# CM4.net
KiCad netlist of a schematic drawn in Altium Designer
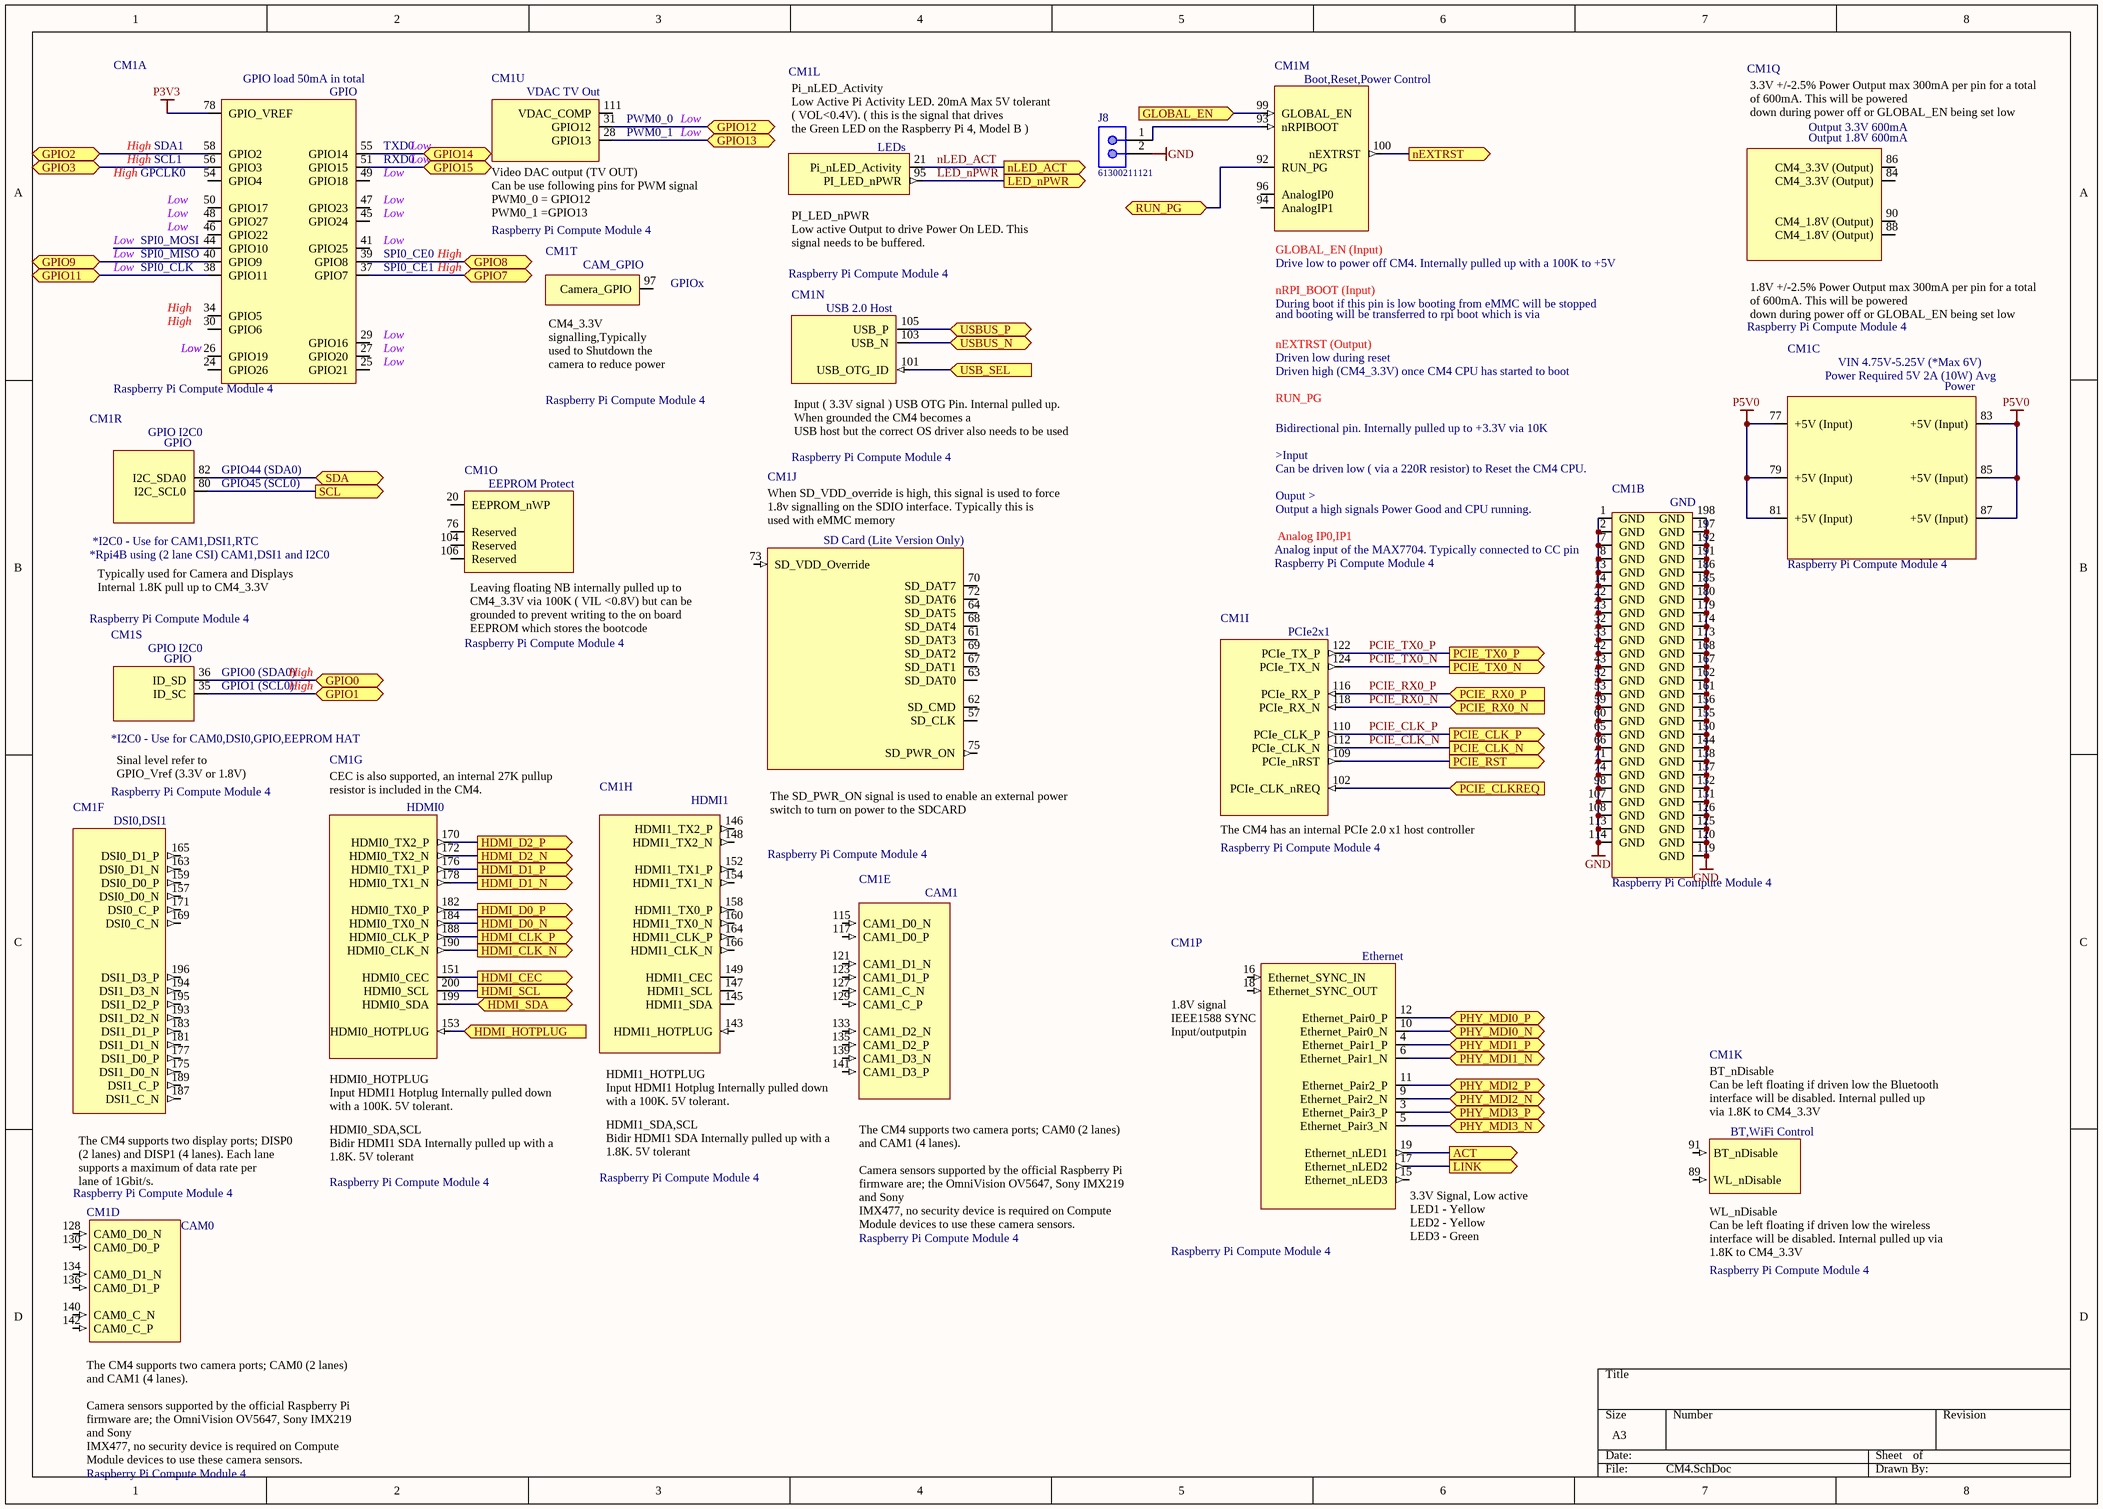
[diagram p0: CM4.SchDoc]

(export (version "E")
  (design (tool "Eeschema 10.0.6"))
  (components
    (comp (ref "CM1")
      (value "Raspberry Pi Compute Module 4")
      (footprint "CM4-DF40HC(3.0)-100DS-0.4v_3mm_1.5mm")
      (description "Raspberry Pi Compute Module 4 by Amornthep Phunsin")
      (libsource (lib "CM4") (part "CM4"))
    )
    (comp (ref "J8")
      (value "61300211121")
      (footprint "61300211121")
      (description "WR-PHD Pin Header, THT, pitch 2.54mm, Single Row, Vertical, 2pin")
      (fields (field (name "PUBLISHER") "Wurth Elektronik"))
      (libsource (lib "ALTIUM-WR-PHD_PIN_HEADER_SOCKET_HEADER-rev19a") (part "61300211121"))
    )
  )
  (nets
    (net (code "1") (name "/ACT") (class "Default")
      (node (ref "CM1") (pin "19") (pinfunction "Ethernet_nLED1_19") (pintype "output"))
    )
    (net (code "2") (name "/GLOBAL_EN") (class "Default")
      (node (ref "CM1") (pin "99") (pinfunction "GLOBAL_EN_99") (pintype "input"))
    )
    (net (code "3") (name "/GPIO0") (class "Default")
      (node (ref "CM1") (pin "36") (pinfunction "ID_SD_36") (pintype "passive"))
    )
    (net (code "4") (name "/GPIO1") (class "Default")
      (node (ref "CM1") (pin "35") (pinfunction "ID_SC_35") (pintype "passive"))
    )
    (net (code "5") (name "/GPIO2") (class "Default")
      (node (ref "CM1") (pin "58") (pinfunction "GPIO2_58") (pintype "passive"))
    )
    (net (code "6") (name "/GPIO3") (class "Default")
      (node (ref "CM1") (pin "56") (pinfunction "GPIO3_56") (pintype "passive"))
    )
    (net (code "7") (name "/GPIO7") (class "Default")
      (node (ref "CM1") (pin "37") (pinfunction "GPIO7_37") (pintype "passive"))
    )
    (net (code "8") (name "/GPIO8") (class "Default")
      (node (ref "CM1") (pin "39") (pinfunction "GPIO8_39") (pintype "passive"))
    )
    (net (code "9") (name "/GPIO9") (class "Default")
      (node (ref "CM1") (pin "40") (pinfunction "GPIO9_40") (pintype "passive"))
    )
    (net (code "10") (name "/GPIO11") (class "Default")
      (node (ref "CM1") (pin "38") (pinfunction "GPIO11_38") (pintype "passive"))
    )
    (net (code "11") (name "/GPIO12") (class "Default")
      (node (ref "CM1") (pin "31") (pinfunction "GPIO12_31") (pintype "passive"))
    )
    (net (code "12") (name "/GPIO13") (class "Default")
      (node (ref "CM1") (pin "28") (pinfunction "GPIO13_28") (pintype "passive"))
    )
    (net (code "13") (name "/GPIO14") (class "Default")
      (node (ref "CM1") (pin "55") (pinfunction "GPIO14_55") (pintype "passive"))
    )
    (net (code "14") (name "/GPIO15") (class "Default")
      (node (ref "CM1") (pin "51") (pinfunction "GPIO15_51") (pintype "passive"))
    )
    (net (code "15") (name "/HDMI_CEC") (class "Default")
      (node (ref "CM1") (pin "151") (pinfunction "HDMI0_CEC_151") (pintype "open_collector"))
    )
    (net (code "16") (name "/HDMI_CLK_N") (class "Default")
      (node (ref "CM1") (pin "190") (pinfunction "HDMI0_CLK_N_190") (pintype "output"))
    )
    (net (code "17") (name "/HDMI_CLK_P") (class "Default")
      (node (ref "CM1") (pin "188") (pinfunction "HDMI0_CLK_P_188") (pintype "output"))
    )
    (net (code "18") (name "/HDMI_D0_N") (class "Default")
      (node (ref "CM1") (pin "184") (pinfunction "HDMI0_TX0_N_184") (pintype "output"))
    )
    (net (code "19") (name "/HDMI_D0_P") (class "Default")
      (node (ref "CM1") (pin "182") (pinfunction "HDMI0_TX0_P_182") (pintype "output"))
    )
    (net (code "20") (name "/HDMI_D1_N") (class "Default")
      (node (ref "CM1") (pin "178") (pinfunction "HDMI0_TX1_N_178") (pintype "output"))
    )
    (net (code "21") (name "/HDMI_D1_P") (class "Default")
      (node (ref "CM1") (pin "176") (pinfunction "HDMI0_TX1_P_176") (pintype "output"))
    )
    (net (code "22") (name "/HDMI_D2_N") (class "Default")
      (node (ref "CM1") (pin "172") (pinfunction "HDMI0_TX2_N_172") (pintype "output"))
    )
    (net (code "23") (name "/HDMI_D2_P") (class "Default")
      (node (ref "CM1") (pin "170") (pinfunction "HDMI0_TX2_P_170") (pintype "output"))
    )
    (net (code "24") (name "/HDMI_HOTPLUG") (class "Default")
      (node (ref "CM1") (pin "153") (pinfunction "HDMI0_HOTPLUG_153") (pintype "input"))
    )
    (net (code "25") (name "/HDMI_SCL") (class "Default")
      (node (ref "CM1") (pin "200") (pinfunction "HDMI0_SCL_200") (pintype "open_collector"))
    )
    (net (code "26") (name "/HDMI_SDA") (class "Default")
      (node (ref "CM1") (pin "199") (pinfunction "HDMI0_SDA_199") (pintype "bidirectional"))
    )
    (net (code "27") (name "/LED_nPWR") (class "Default")
      (node (ref "CM1") (pin "95") (pinfunction "PI_LED_nPWR_95") (pintype "output"))
    )
    (net (code "28") (name "/LINK") (class "Default")
      (node (ref "CM1") (pin "17") (pinfunction "Ethernet_nLED2_17") (pintype "output"))
    )
    (net (code "29") (name "/PCIE_CLKREQ") (class "Default")
      (node (ref "CM1") (pin "102") (pinfunction "PCIe_CLK_nREQ_102") (pintype "input"))
    )
    (net (code "30") (name "/PCIE_CLK_N") (class "Default")
      (node (ref "CM1") (pin "112") (pinfunction "PCIe_CLK_N_112") (pintype "output"))
    )
    (net (code "31") (name "/PCIE_CLK_P") (class "Default")
      (node (ref "CM1") (pin "110") (pinfunction "PCIe_CLK_P_110") (pintype "output"))
    )
    (net (code "32") (name "/PCIE_RST") (class "Default")
      (node (ref "CM1") (pin "109") (pinfunction "PCIe_nRST_109") (pintype "output"))
    )
    (net (code "33") (name "/PCIE_RX0_N") (class "Default")
      (node (ref "CM1") (pin "118") (pinfunction "PCIe_RX_N_118") (pintype "input"))
    )
    (net (code "34") (name "/PCIE_RX0_P") (class "Default")
      (node (ref "CM1") (pin "116") (pinfunction "PCIe_RX_P_116") (pintype "input"))
    )
    (net (code "35") (name "/PCIE_TX0_N") (class "Default")
      (node (ref "CM1") (pin "124") (pinfunction "PCIe_TX_N_124") (pintype "output"))
    )
    (net (code "36") (name "/PCIE_TX0_P") (class "Default")
      (node (ref "CM1") (pin "122") (pinfunction "PCIe_TX_P_122") (pintype "output"))
    )
    (net (code "37") (name "/PHY_MDI0_N") (class "Default")
      (node (ref "CM1") (pin "10") (pinfunction "Ethernet_Pair0_N_10") (pintype "passive"))
    )
    (net (code "38") (name "/PHY_MDI0_P") (class "Default")
      (node (ref "CM1") (pin "12") (pinfunction "Ethernet_Pair0_P_12") (pintype "passive"))
    )
    (net (code "39") (name "/PHY_MDI1_N") (class "Default")
      (node (ref "CM1") (pin "6") (pinfunction "Ethernet_Pair1_N_6") (pintype "passive"))
    )
    (net (code "40") (name "/PHY_MDI1_P") (class "Default")
      (node (ref "CM1") (pin "4") (pinfunction "Ethernet_Pair1_P_4") (pintype "passive"))
    )
    (net (code "41") (name "/PHY_MDI2_N") (class "Default")
      (node (ref "CM1") (pin "9") (pinfunction "Ethernet_Pair2_N_9") (pintype "passive"))
    )
    (net (code "42") (name "/PHY_MDI2_P") (class "Default")
      (node (ref "CM1") (pin "11") (pinfunction "Ethernet_Pair2_P_11") (pintype "passive"))
    )
    (net (code "43") (name "/PHY_MDI3_N") (class "Default")
      (node (ref "CM1") (pin "5") (pinfunction "Ethernet_Pair3_N_5") (pintype "passive"))
    )
    (net (code "44") (name "/PHY_MDI3_P") (class "Default")
      (node (ref "CM1") (pin "3") (pinfunction "Ethernet_Pair3_P_3") (pintype "passive"))
    )
    (net (code "45") (name "/RUN_PG") (class "Default")
      (node (ref "CM1") (pin "92") (pinfunction "RUN_PG_92") (pintype "passive"))
    )
    (net (code "46") (name "/SCL") (class "Default")
      (node (ref "CM1") (pin "80") (pinfunction "I2C_SCL0_80") (pintype "passive"))
    )
    (net (code "47") (name "/SDA") (class "Default")
      (node (ref "CM1") (pin "82") (pinfunction "I2C_SDA0_82") (pintype "passive"))
    )
    (net (code "48") (name "/USBUS_N") (class "Default")
      (node (ref "CM1") (pin "103") (pinfunction "USB_N_103") (pintype "passive"))
    )
    (net (code "49") (name "/USBUS_P") (class "Default")
      (node (ref "CM1") (pin "105") (pinfunction "USB_P_105") (pintype "passive"))
    )
    (net (code "50") (name "/USB_SEL") (class "Default")
      (node (ref "CM1") (pin "101") (pinfunction "USB_OTG_ID_101") (pintype "input"))
    )
    (net (code "51") (name "/nEXTRST") (class "Default")
      (node (ref "CM1") (pin "100") (pinfunction "nEXTRST_100") (pintype "output"))
    )
    (net (code "52") (name "/nLED_ACT") (class "Default")
      (node (ref "CM1") (pin "21") (pinfunction "Pi_nLED_Activity_21") (pintype "open_collector"))
    )
    (net (code "53") (name "GND") (class "Default")
      (node (ref "CM1") (pin "1") (pinfunction "GND_1") (pintype "power_in"))
      (node (ref "CM1") (pin "107") (pinfunction "GND_107") (pintype "power_in"))
      (node (ref "CM1") (pin "108") (pinfunction "GND_108") (pintype "power_in"))
      (node (ref "CM1") (pin "113") (pinfunction "GND_113") (pintype "power_in"))
      (node (ref "CM1") (pin "114") (pinfunction "GND_114") (pintype "power_in"))
      (node (ref "CM1") (pin "119") (pinfunction "GND_119") (pintype "power_in"))
      (node (ref "CM1") (pin "120") (pinfunction "GND_120") (pintype "power_in"))
      (node (ref "CM1") (pin "125") (pinfunction "GND_125") (pintype "power_in"))
      (node (ref "CM1") (pin "126") (pinfunction "GND_126") (pintype "power_in"))
      (node (ref "CM1") (pin "13") (pinfunction "GND_13") (pintype "power_in"))
      (node (ref "CM1") (pin "131") (pinfunction "GND_131") (pintype "power_in"))
      (node (ref "CM1") (pin "132") (pinfunction "GND_132") (pintype "power_in"))
      (node (ref "CM1") (pin "137") (pinfunction "GND_137") (pintype "power_in"))
      (node (ref "CM1") (pin "138") (pinfunction "GND_138") (pintype "power_in"))
      (node (ref "CM1") (pin "14") (pinfunction "GND_14") (pintype "power_in"))
      (node (ref "CM1") (pin "144") (pinfunction "GND_144") (pintype "power_in"))
      (node (ref "CM1") (pin "150") (pinfunction "GND_150") (pintype "power_in"))
      (node (ref "CM1") (pin "155") (pinfunction "GND_155") (pintype "power_in"))
      (node (ref "CM1") (pin "156") (pinfunction "GND_156") (pintype "power_in"))
      (node (ref "CM1") (pin "161") (pinfunction "GND_161") (pintype "power_in"))
      (node (ref "CM1") (pin "162") (pinfunction "GND_162") (pintype "power_in"))
      (node (ref "CM1") (pin "167") (pinfunction "GND_167") (pintype "power_in"))
      (node (ref "CM1") (pin "168") (pinfunction "GND_168") (pintype "power_in"))
      (node (ref "CM1") (pin "173") (pinfunction "GND_173") (pintype "power_in"))
      (node (ref "CM1") (pin "174") (pinfunction "GND_174") (pintype "power_in"))
      (node (ref "CM1") (pin "179") (pinfunction "GND_179") (pintype "power_in"))
      (node (ref "CM1") (pin "180") (pinfunction "GND_180") (pintype "power_in"))
      (node (ref "CM1") (pin "185") (pinfunction "GND_185") (pintype "power_in"))
      (node (ref "CM1") (pin "186") (pinfunction "GND_186") (pintype "power_in"))
      (node (ref "CM1") (pin "191") (pinfunction "GND_191") (pintype "power_in"))
      (node (ref "CM1") (pin "192") (pinfunction "GND_192") (pintype "power_in"))
      (node (ref "CM1") (pin "197") (pinfunction "GND_197") (pintype "power_in"))
      (node (ref "CM1") (pin "198") (pinfunction "GND_198") (pintype "power_in"))
      (node (ref "CM1") (pin "2") (pinfunction "GND_2") (pintype "power_in"))
      (node (ref "CM1") (pin "22") (pinfunction "GND_22") (pintype "power_in"))
      (node (ref "CM1") (pin "23") (pinfunction "GND_23") (pintype "power_in"))
      (node (ref "CM1") (pin "32") (pinfunction "GND_32") (pintype "power_in"))
      (node (ref "CM1") (pin "33") (pinfunction "GND_33") (pintype "power_in"))
      (node (ref "CM1") (pin "42") (pinfunction "GND_42") (pintype "power_in"))
      (node (ref "CM1") (pin "43") (pinfunction "GND_43") (pintype "power_in"))
      (node (ref "CM1") (pin "52") (pinfunction "GND_52") (pintype "power_in"))
      (node (ref "CM1") (pin "53") (pinfunction "GND_53") (pintype "power_in"))
      (node (ref "CM1") (pin "59") (pinfunction "GND_59") (pintype "power_in"))
      (node (ref "CM1") (pin "60") (pinfunction "GND_60") (pintype "power_in"))
      (node (ref "CM1") (pin "65") (pinfunction "GND_65") (pintype "power_in"))
      (node (ref "CM1") (pin "66") (pinfunction "GND_66") (pintype "power_in"))
      (node (ref "CM1") (pin "7") (pinfunction "GND_7") (pintype "power_in"))
      (node (ref "CM1") (pin "71") (pinfunction "GND_71") (pintype "power_in"))
      (node (ref "CM1") (pin "74") (pinfunction "GND_74") (pintype "power_in"))
      (node (ref "CM1") (pin "8") (pinfunction "GND_8") (pintype "power_in"))
      (node (ref "CM1") (pin "98") (pinfunction "GND_98") (pintype "power_in"))
      (node (ref "J8") (pin "2") (pinfunction "2_2") (pintype "passive"))
    )
    (net (code "54") (name "Net-(CM1M-nRPIBOOT)") (class "Default")
      (node (ref "CM1") (pin "93") (pinfunction "nRPIBOOT_93") (pintype "input"))
      (node (ref "J8") (pin "1") (pinfunction "1_1") (pintype "passive"))
    )
    (net (code "55") (name "P3V3") (class "Default")
      (node (ref "CM1") (pin "78") (pinfunction "GPIO_VREF_78") (pintype "power_in"))
    )
    (net (code "56") (name "P5V0") (class "Default")
      (node (ref "CM1") (pin "77") (pinfunction "+5V_(Input)_77") (pintype "power_in"))
      (node (ref "CM1") (pin "79") (pinfunction "+5V_(Input)_79") (pintype "power_in"))
      (node (ref "CM1") (pin "81") (pinfunction "+5V_(Input)_81") (pintype "power_in"))
      (node (ref "CM1") (pin "83") (pinfunction "+5V_(Input)_83") (pintype "power_in"))
      (node (ref "CM1") (pin "85") (pinfunction "+5V_(Input)_85") (pintype "power_in"))
      (node (ref "CM1") (pin "87") (pinfunction "+5V_(Input)_87") (pintype "power_in"))
    )
    (net (code "57") (name "unconnected-(CM1A-GPIO4-Pad54)") (class "Default")
      (node (ref "CM1") (pin "54") (pinfunction "GPIO4_54") (pintype "passive"))
    )
    (net (code "58") (name "unconnected-(CM1A-GPIO5-Pad34)") (class "Default")
      (node (ref "CM1") (pin "34") (pinfunction "GPIO5_34") (pintype "passive"))
    )
    (net (code "59") (name "unconnected-(CM1A-GPIO6-Pad30)") (class "Default")
      (node (ref "CM1") (pin "30") (pinfunction "GPIO6_30") (pintype "passive"))
    )
    (net (code "60") (name "unconnected-(CM1A-GPIO10-Pad44)") (class "Default")
      (node (ref "CM1") (pin "44") (pinfunction "GPIO10_44") (pintype "passive"))
    )
    (net (code "61") (name "unconnected-(CM1A-GPIO16-Pad29)") (class "Default")
      (node (ref "CM1") (pin "29") (pinfunction "GPIO16_29") (pintype "passive"))
    )
    (net (code "62") (name "unconnected-(CM1A-GPIO17-Pad50)") (class "Default")
      (node (ref "CM1") (pin "50") (pinfunction "GPIO17_50") (pintype "passive"))
    )
    (net (code "63") (name "unconnected-(CM1A-GPIO18-Pad49)") (class "Default")
      (node (ref "CM1") (pin "49") (pinfunction "GPIO18_49") (pintype "passive"))
    )
    (net (code "64") (name "unconnected-(CM1A-GPIO19-Pad26)") (class "Default")
      (node (ref "CM1") (pin "26") (pinfunction "GPIO19_26") (pintype "passive"))
    )
    (net (code "65") (name "unconnected-(CM1A-GPIO20-Pad27)") (class "Default")
      (node (ref "CM1") (pin "27") (pinfunction "GPIO20_27") (pintype "passive"))
    )
    (net (code "66") (name "unconnected-(CM1A-GPIO21-Pad25)") (class "Default")
      (node (ref "CM1") (pin "25") (pinfunction "GPIO21_25") (pintype "passive"))
    )
    (net (code "67") (name "unconnected-(CM1A-GPIO22-Pad46)") (class "Default")
      (node (ref "CM1") (pin "46") (pinfunction "GPIO22_46") (pintype "passive"))
    )
    (net (code "68") (name "unconnected-(CM1A-GPIO23-Pad47)") (class "Default")
      (node (ref "CM1") (pin "47") (pinfunction "GPIO23_47") (pintype "passive"))
    )
    (net (code "69") (name "unconnected-(CM1A-GPIO24-Pad45)") (class "Default")
      (node (ref "CM1") (pin "45") (pinfunction "GPIO24_45") (pintype "passive"))
    )
    (net (code "70") (name "unconnected-(CM1A-GPIO25-Pad41)") (class "Default")
      (node (ref "CM1") (pin "41") (pinfunction "GPIO25_41") (pintype "passive"))
    )
    (net (code "71") (name "unconnected-(CM1A-GPIO26-Pad24)") (class "Default")
      (node (ref "CM1") (pin "24") (pinfunction "GPIO26_24") (pintype "passive"))
    )
    (net (code "72") (name "unconnected-(CM1A-GPIO27-Pad48)") (class "Default")
      (node (ref "CM1") (pin "48") (pinfunction "GPIO27_48") (pintype "passive"))
    )
    (net (code "73") (name "unconnected-(CM1D-CAM0_C_N-Pad140)") (class "Default")
      (node (ref "CM1") (pin "140") (pinfunction "CAM0_C_N_140") (pintype "input"))
    )
    (net (code "74") (name "unconnected-(CM1D-CAM0_C_P-Pad142)") (class "Default")
      (node (ref "CM1") (pin "142") (pinfunction "CAM0_C_P_142") (pintype "input"))
    )
    (net (code "75") (name "unconnected-(CM1D-CAM0_D0_N-Pad128)") (class "Default")
      (node (ref "CM1") (pin "128") (pinfunction "CAM0_D0_N_128") (pintype "input"))
    )
    (net (code "76") (name "unconnected-(CM1D-CAM0_D0_P-Pad130)") (class "Default")
      (node (ref "CM1") (pin "130") (pinfunction "CAM0_D0_P_130") (pintype "input"))
    )
    (net (code "77") (name "unconnected-(CM1D-CAM0_D1_N-Pad134)") (class "Default")
      (node (ref "CM1") (pin "134") (pinfunction "CAM0_D1_N_134") (pintype "input"))
    )
    (net (code "78") (name "unconnected-(CM1D-CAM0_D1_P-Pad136)") (class "Default")
      (node (ref "CM1") (pin "136") (pinfunction "CAM0_D1_P_136") (pintype "input"))
    )
    (net (code "79") (name "unconnected-(CM1E-CAM1_C_N-Pad127)") (class "Default")
      (node (ref "CM1") (pin "127") (pinfunction "CAM1_C_N_127") (pintype "input"))
    )
    (net (code "80") (name "unconnected-(CM1E-CAM1_C_P-Pad129)") (class "Default")
      (node (ref "CM1") (pin "129") (pinfunction "CAM1_C_P_129") (pintype "input"))
    )
    (net (code "81") (name "unconnected-(CM1E-CAM1_D0_N-Pad115)") (class "Default")
      (node (ref "CM1") (pin "115") (pinfunction "CAM1_D0_N_115") (pintype "input"))
    )
    (net (code "82") (name "unconnected-(CM1E-CAM1_D0_P-Pad117)") (class "Default")
      (node (ref "CM1") (pin "117") (pinfunction "CAM1_D0_P_117") (pintype "input"))
    )
    (net (code "83") (name "unconnected-(CM1E-CAM1_D1_N-Pad121)") (class "Default")
      (node (ref "CM1") (pin "121") (pinfunction "CAM1_D1_N_121") (pintype "input"))
    )
    (net (code "84") (name "unconnected-(CM1E-CAM1_D1_P-Pad123)") (class "Default")
      (node (ref "CM1") (pin "123") (pinfunction "CAM1_D1_P_123") (pintype "input"))
    )
    (net (code "85") (name "unconnected-(CM1E-CAM1_D2_N-Pad133)") (class "Default")
      (node (ref "CM1") (pin "133") (pinfunction "CAM1_D2_N_133") (pintype "input"))
    )
    (net (code "86") (name "unconnected-(CM1E-CAM1_D2_P-Pad135)") (class "Default")
      (node (ref "CM1") (pin "135") (pinfunction "CAM1_D2_P_135") (pintype "input"))
    )
    (net (code "87") (name "unconnected-(CM1E-CAM1_D3_N-Pad139)") (class "Default")
      (node (ref "CM1") (pin "139") (pinfunction "CAM1_D3_N_139") (pintype "input"))
    )
    (net (code "88") (name "unconnected-(CM1E-CAM1_D3_P-Pad141)") (class "Default")
      (node (ref "CM1") (pin "141") (pinfunction "CAM1_D3_P_141") (pintype "input"))
    )
    (net (code "89") (name "unconnected-(CM1F-DSI0_C_N-Pad169)") (class "Default")
      (node (ref "CM1") (pin "169") (pinfunction "DSI0_C_N_169") (pintype "output"))
    )
    (net (code "90") (name "unconnected-(CM1F-DSI0_C_P-Pad171)") (class "Default")
      (node (ref "CM1") (pin "171") (pinfunction "DSI0_C_P_171") (pintype "output"))
    )
    (net (code "91") (name "unconnected-(CM1F-DSI0_D0_N-Pad157)") (class "Default")
      (node (ref "CM1") (pin "157") (pinfunction "DSI0_D0_N_157") (pintype "output"))
    )
    (net (code "92") (name "unconnected-(CM1F-DSI0_D0_P-Pad159)") (class "Default")
      (node (ref "CM1") (pin "159") (pinfunction "DSI0_D0_P_159") (pintype "output"))
    )
    (net (code "93") (name "unconnected-(CM1F-DSI0_D1_N-Pad163)") (class "Default")
      (node (ref "CM1") (pin "163") (pinfunction "DSI0_D1_N_163") (pintype "output"))
    )
    (net (code "94") (name "unconnected-(CM1F-DSI0_D1_P-Pad165)") (class "Default")
      (node (ref "CM1") (pin "165") (pinfunction "DSI0_D1_P_165") (pintype "output"))
    )
    (net (code "95") (name "unconnected-(CM1F-DSI1_C_N-Pad187)") (class "Default")
      (node (ref "CM1") (pin "187") (pinfunction "DSI1_C_N_187") (pintype "output"))
    )
    (net (code "96") (name "unconnected-(CM1F-DSI1_C_P-Pad189)") (class "Default")
      (node (ref "CM1") (pin "189") (pinfunction "DSI1_C_P_189") (pintype "output"))
    )
    (net (code "97") (name "unconnected-(CM1F-DSI1_D0_N-Pad175)") (class "Default")
      (node (ref "CM1") (pin "175") (pinfunction "DSI1_D0_N_175") (pintype "output"))
    )
    (net (code "98") (name "unconnected-(CM1F-DSI1_D0_P-Pad177)") (class "Default")
      (node (ref "CM1") (pin "177") (pinfunction "DSI1_D0_P_177") (pintype "output"))
    )
    (net (code "99") (name "unconnected-(CM1F-DSI1_D1_N-Pad181)") (class "Default")
      (node (ref "CM1") (pin "181") (pinfunction "DSI1_D1_N_181") (pintype "output"))
    )
    (net (code "100") (name "unconnected-(CM1F-DSI1_D1_P-Pad183)") (class "Default")
      (node (ref "CM1") (pin "183") (pinfunction "DSI1_D1_P_183") (pintype "output"))
    )
    (net (code "101") (name "unconnected-(CM1F-DSI1_D2_N-Pad193)") (class "Default")
      (node (ref "CM1") (pin "193") (pinfunction "DSI1_D2_N_193") (pintype "output"))
    )
    (net (code "102") (name "unconnected-(CM1F-DSI1_D2_P-Pad195)") (class "Default")
      (node (ref "CM1") (pin "195") (pinfunction "DSI1_D2_P_195") (pintype "output"))
    )
    (net (code "103") (name "unconnected-(CM1F-DSI1_D3_N-Pad194)") (class "Default")
      (node (ref "CM1") (pin "194") (pinfunction "DSI1_D3_N_194") (pintype "output"))
    )
    (net (code "104") (name "unconnected-(CM1F-DSI1_D3_P-Pad196)") (class "Default")
      (node (ref "CM1") (pin "196") (pinfunction "DSI1_D3_P_196") (pintype "output"))
    )
    (net (code "105") (name "unconnected-(CM1H-HDMI1_CEC-Pad149)") (class "Default")
      (node (ref "CM1") (pin "149") (pinfunction "HDMI1_CEC_149") (pintype "open_collector"))
    )
    (net (code "106") (name "unconnected-(CM1H-HDMI1_CLK_N-Pad166)") (class "Default")
      (node (ref "CM1") (pin "166") (pinfunction "HDMI1_CLK_N_166") (pintype "output"))
    )
    (net (code "107") (name "unconnected-(CM1H-HDMI1_CLK_P-Pad164)") (class "Default")
      (node (ref "CM1") (pin "164") (pinfunction "HDMI1_CLK_P_164") (pintype "output"))
    )
    (net (code "108") (name "unconnected-(CM1H-HDMI1_HOTPLUG-Pad143)") (class "Default")
      (node (ref "CM1") (pin "143") (pinfunction "HDMI1_HOTPLUG_143") (pintype "input"))
    )
    (net (code "109") (name "unconnected-(CM1H-HDMI1_SCL-Pad147)") (class "Default")
      (node (ref "CM1") (pin "147") (pinfunction "HDMI1_SCL_147") (pintype "open_collector"))
    )
    (net (code "110") (name "unconnected-(CM1H-HDMI1_SDA-Pad145)") (class "Default")
      (node (ref "CM1") (pin "145") (pinfunction "HDMI1_SDA_145") (pintype "bidirectional"))
    )
    (net (code "111") (name "unconnected-(CM1H-HDMI1_TX0_N-Pad160)") (class "Default")
      (node (ref "CM1") (pin "160") (pinfunction "HDMI1_TX0_N_160") (pintype "output"))
    )
    (net (code "112") (name "unconnected-(CM1H-HDMI1_TX0_P-Pad158)") (class "Default")
      (node (ref "CM1") (pin "158") (pinfunction "HDMI1_TX0_P_158") (pintype "output"))
    )
    (net (code "113") (name "unconnected-(CM1H-HDMI1_TX1_N-Pad154)") (class "Default")
      (node (ref "CM1") (pin "154") (pinfunction "HDMI1_TX1_N_154") (pintype "output"))
    )
    (net (code "114") (name "unconnected-(CM1H-HDMI1_TX1_P-Pad152)") (class "Default")
      (node (ref "CM1") (pin "152") (pinfunction "HDMI1_TX1_P_152") (pintype "output"))
    )
    (net (code "115") (name "unconnected-(CM1H-HDMI1_TX2_N-Pad148)") (class "Default")
      (node (ref "CM1") (pin "148") (pinfunction "HDMI1_TX2_N_148") (pintype "output"))
    )
    (net (code "116") (name "unconnected-(CM1H-HDMI1_TX2_P-Pad146)") (class "Default")
      (node (ref "CM1") (pin "146") (pinfunction "HDMI1_TX2_P_146") (pintype "output"))
    )
    (net (code "117") (name "unconnected-(CM1J-SD_CLK-Pad57)") (class "Default")
      (node (ref "CM1") (pin "57") (pinfunction "SD_CLK_57") (pintype "passive"))
    )
    (net (code "118") (name "unconnected-(CM1J-SD_CMD-Pad62)") (class "Default")
      (node (ref "CM1") (pin "62") (pinfunction "SD_CMD_62") (pintype "passive"))
    )
    (net (code "119") (name "unconnected-(CM1J-SD_DAT0-Pad63)") (class "Default")
      (node (ref "CM1") (pin "63") (pinfunction "SD_DAT0_63") (pintype "passive"))
    )
    (net (code "120") (name "unconnected-(CM1J-SD_DAT1-Pad67)") (class "Default")
      (node (ref "CM1") (pin "67") (pinfunction "SD_DAT1_67") (pintype "passive"))
    )
    (net (code "121") (name "unconnected-(CM1J-SD_DAT2-Pad69)") (class "Default")
      (node (ref "CM1") (pin "69") (pinfunction "SD_DAT2_69") (pintype "passive"))
    )
    (net (code "122") (name "unconnected-(CM1J-SD_DAT3-Pad61)") (class "Default")
      (node (ref "CM1") (pin "61") (pinfunction "SD_DAT3_61") (pintype "passive"))
    )
    (net (code "123") (name "unconnected-(CM1J-SD_DAT4-Pad68)") (class "Default")
      (node (ref "CM1") (pin "68") (pinfunction "SD_DAT4_68") (pintype "passive"))
    )
    (net (code "124") (name "unconnected-(CM1J-SD_DAT5-Pad64)") (class "Default")
      (node (ref "CM1") (pin "64") (pinfunction "SD_DAT5_64") (pintype "passive"))
    )
    (net (code "125") (name "unconnected-(CM1J-SD_DAT6-Pad72)") (class "Default")
      (node (ref "CM1") (pin "72") (pinfunction "SD_DAT6_72") (pintype "passive"))
    )
    (net (code "126") (name "unconnected-(CM1J-SD_DAT7-Pad70)") (class "Default")
      (node (ref "CM1") (pin "70") (pinfunction "SD_DAT7_70") (pintype "passive"))
    )
    (net (code "127") (name "unconnected-(CM1J-SD_PWR_ON-Pad75)") (class "Default")
      (node (ref "CM1") (pin "75") (pinfunction "SD_PWR_ON_75") (pintype "output"))
    )
    (net (code "128") (name "unconnected-(CM1J-SD_VDD_Override-Pad73)") (class "Default")
      (node (ref "CM1") (pin "73") (pinfunction "SD_VDD_Override_73") (pintype "input"))
    )
    (net (code "129") (name "unconnected-(CM1K-BT_nDisable-Pad91)") (class "Default")
      (node (ref "CM1") (pin "91") (pinfunction "BT_nDisable_91") (pintype "input"))
    )
    (net (code "130") (name "unconnected-(CM1K-WL_nDisable-Pad89)") (class "Default")
      (node (ref "CM1") (pin "89") (pinfunction "WL_nDisable_89") (pintype "input"))
    )
    (net (code "131") (name "unconnected-(CM1M-AnalogIP0-Pad96)") (class "Default")
      (node (ref "CM1") (pin "96") (pinfunction "AnalogIP0_96") (pintype "passive"))
    )
    (net (code "132") (name "unconnected-(CM1M-AnalogIP1-Pad94)") (class "Default")
      (node (ref "CM1") (pin "94") (pinfunction "AnalogIP1_94") (pintype "passive"))
    )
    (net (code "133") (name "unconnected-(CM1O-EEPROM_nWP-Pad20)") (class "Default")
      (node (ref "CM1") (pin "20") (pinfunction "EEPROM_nWP_20") (pintype "passive"))
    )
    (net (code "134") (name "unconnected-(CM1O-Reserved-Pad76)") (class "Default")
      (node (ref "CM1") (pin "76") (pinfunction "Reserved_76") (pintype "passive"))
    )
    (net (code "135") (name "unconnected-(CM1O-Reserved-Pad104)") (class "Default")
      (node (ref "CM1") (pin "104") (pinfunction "Reserved_104") (pintype "passive"))
    )
    (net (code "136") (name "unconnected-(CM1O-Reserved-Pad106)") (class "Default")
      (node (ref "CM1") (pin "106") (pinfunction "Reserved_106") (pintype "passive"))
    )
    (net (code "137") (name "unconnected-(CM1P-Ethernet_SYNC_IN-Pad16)") (class "Default")
      (node (ref "CM1") (pin "16") (pinfunction "Ethernet_SYNC_IN_16") (pintype "input"))
    )
    (net (code "138") (name "unconnected-(CM1P-Ethernet_SYNC_OUT-Pad18)") (class "Default")
      (node (ref "CM1") (pin "18") (pinfunction "Ethernet_SYNC_OUT_18") (pintype "input"))
    )
    (net (code "139") (name "unconnected-(CM1P-Ethernet_nLED3-Pad15)") (class "Default")
      (node (ref "CM1") (pin "15") (pinfunction "Ethernet_nLED3_15") (pintype "output"))
    )
    (net (code "140") (name "unconnected-(CM1Q-CM4_1.8V_(Output)-Pad88)") (class "Default")
      (node (ref "CM1") (pin "88") (pinfunction "CM4_1.8V_(Output)_88") (pintype "power_in"))
    )
    (net (code "141") (name "unconnected-(CM1Q-CM4_1.8V_(Output)-Pad90)") (class "Default")
      (node (ref "CM1") (pin "90") (pinfunction "CM4_1.8V_(Output)_90") (pintype "power_in"))
    )
    (net (code "142") (name "unconnected-(CM1Q-CM4_3.3V_(Output)-Pad84)") (class "Default")
      (node (ref "CM1") (pin "84") (pinfunction "CM4_3.3V_(Output)_84") (pintype "power_in"))
    )
    (net (code "143") (name "unconnected-(CM1Q-CM4_3.3V_(Output)-Pad86)") (class "Default")
      (node (ref "CM1") (pin "86") (pinfunction "CM4_3.3V_(Output)_86") (pintype "power_in"))
    )
    (net (code "144") (name "unconnected-(CM1T-Camera_GPIO-Pad97)") (class "Default")
      (node (ref "CM1") (pin "97") (pinfunction "Camera_GPIO_97") (pintype "passive"))
    )
    (net (code "145") (name "unconnected-(CM1U-VDAC_COMP-Pad111)") (class "Default")
      (node (ref "CM1") (pin "111") (pinfunction "VDAC_COMP_111") (pintype "passive"))
    )
  )
)
